# USB3_0_Console.net
KiCad netlist of a schematic drawn in Altium Designer
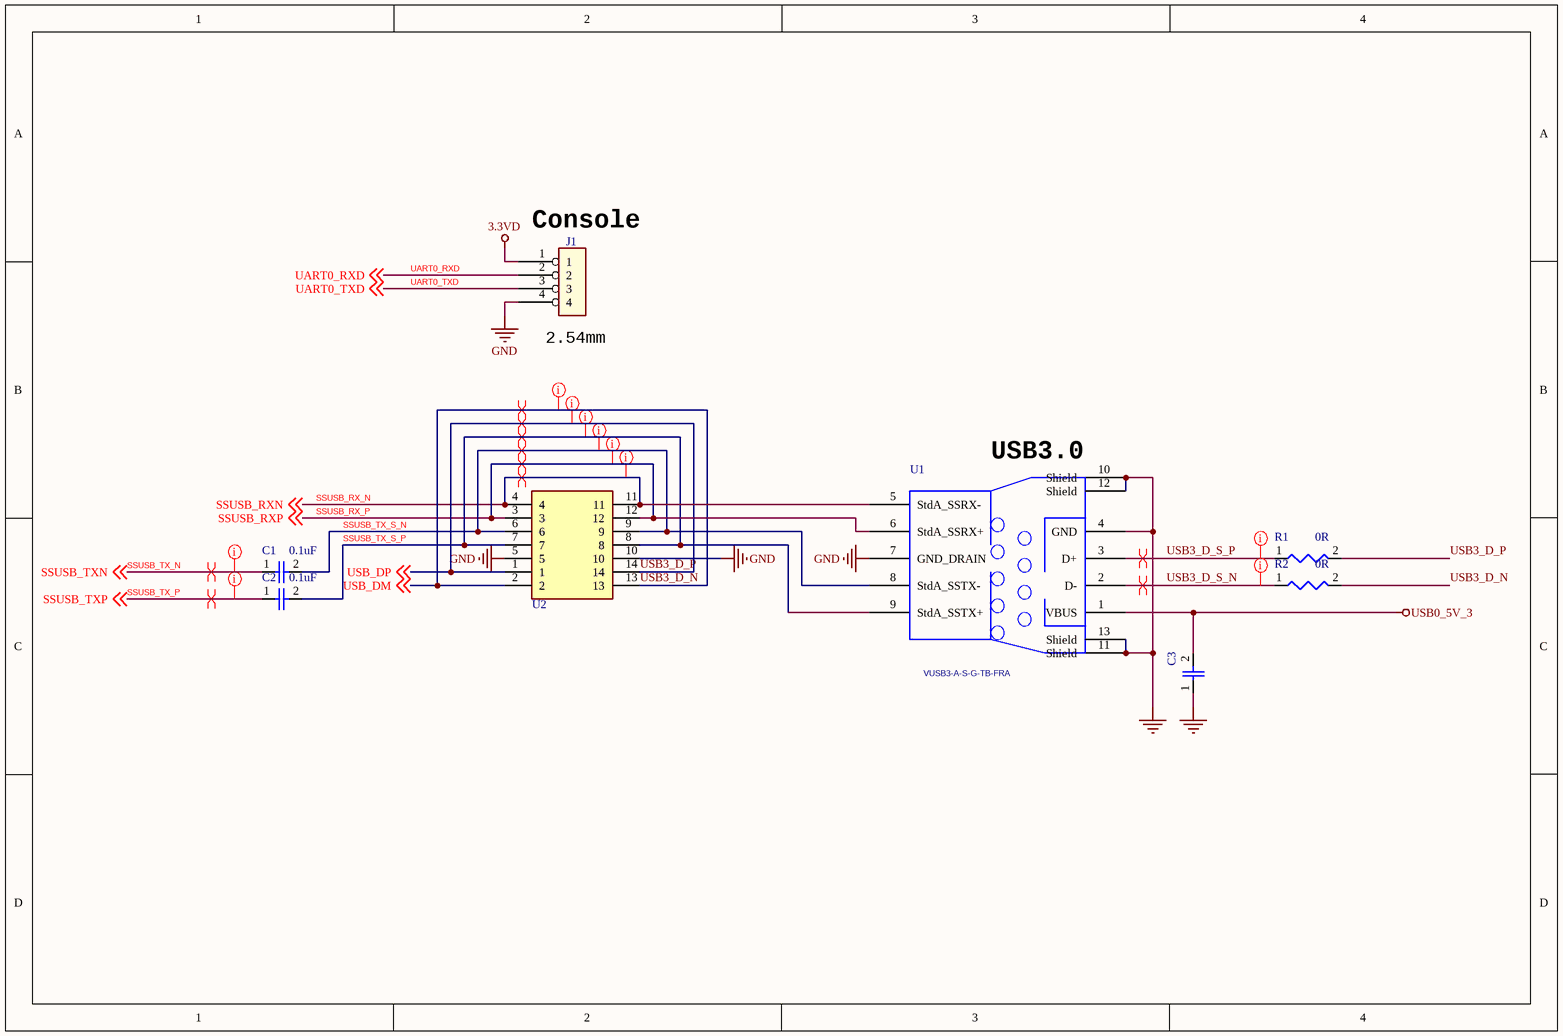
[diagram p0: USB3.0_Console.SchDoc]

(export (version "E")
  (design (tool "Eeschema 10.0.6"))
  (components
    (comp (ref "C1") (value "0.1uF") (footprint "0402-C") (libsource (lib "OOLITEV8") (part "CAP")))
    (comp (ref "C2") (value "0.1uF") (footprint "0402-C") (libsource (lib "OOLITEV8") (part "CAP")))
    (comp (ref "C3") (value "22uF,10V,0805") (footprint "0805-C") (libsource (lib "OOLITEV8") (part "CAP")))
    (comp (ref "J1")
      (value "HEADER 4x1")
      (footprint "CONN_4X1")
      (libsource (lib "OOLITEV8") (part "HEADER 4x1"))
    )
    (comp (ref "R1") (value "0R") (footprint "0402-R") (libsource (lib "OOLITEV8") (part "Res")))
    (comp (ref "R2") (value "0R") (footprint "0402-R") (libsource (lib "OOLITEV8") (part "Res")))
    (comp (ref "U1")
      (value "VUSB3-A-S-G-TB-FRA")
      (footprint "VALCON_VUSB3-A-S-G-TB-FRA")
      (description "USB 3 Type A Right Angle Vertical Socket")
      (libsource (lib "OOLITEV8") (part "VUSB3-A-S-G-TB-FRA"))
    )
    (comp (ref "U2")
      (value "SP3011-06UTG")
      (footprint "SON50P350X135X55-14N")
      (description "7V _Typ_ Clamp 4A _8/20Âµs_ Ipp Tvs Diode Surface Mount 14-UDFN _3.5x1.35_")
      (fields (field (name "MP") "SP3012-06UTG") (field (name "MF") "Littelfuse Inc."))
      (libsource (lib "OOLITEV8") (part "SP3012-06UTG"))
    )
  )
  (nets
    (net (code "1") (name "/SSUSB_TX_S_N") (class "Default")
      (node (ref "C1") (pin "2") (pinfunction "2_2") (pintype "passive"))
      (node (ref "U1") (pin "8") (pinfunction "StdA_SSTX-_8") (pintype "passive"))
      (node (ref "U2") (pin "6") (pinfunction "6_6") (pintype "passive"))
      (node (ref "U2") (pin "9") (pinfunction "9_9") (pintype "passive"))
    )
    (net (code "2") (name "/SSUSB_TX_S_P") (class "Default")
      (node (ref "C2") (pin "2") (pinfunction "2_2") (pintype "passive"))
      (node (ref "U1") (pin "9") (pinfunction "StdA_SSTX+_9") (pintype "passive"))
      (node (ref "U2") (pin "7") (pinfunction "7_7") (pintype "passive"))
      (node (ref "U2") (pin "8") (pinfunction "8_8") (pintype "passive"))
    )
    (net (code "3") (name "/USB3_D_S_N") (class "Default")
      (node (ref "R2") (pin "1") (pinfunction "1_1") (pintype "passive"))
      (node (ref "U1") (pin "2") (pinfunction "D-_2") (pintype "passive"))
    )
    (net (code "4") (name "/USB3_D_S_P") (class "Default")
      (node (ref "R1") (pin "1") (pinfunction "1_1") (pintype "passive"))
      (node (ref "U1") (pin "3") (pinfunction "D+_3") (pintype "passive"))
    )
    (net (code "5") (name "3.3VD") (class "Default")
      (node (ref "J1") (pin "1") (pinfunction "1_1") (pintype "passive"))
    )
    (net (code "6") (name "GND") (class "Default")
      (node (ref "C3") (pin "1") (pinfunction "1_1") (pintype "passive"))
      (node (ref "J1") (pin "4") (pinfunction "4_4") (pintype "passive"))
      (node (ref "U1") (pin "10") (pinfunction "Shield_10") (pintype "passive"))
      (node (ref "U1") (pin "11") (pinfunction "Shield_11") (pintype "passive"))
      (node (ref "U1") (pin "12") (pinfunction "Shield_12") (pintype "passive"))
      (node (ref "U1") (pin "13") (pinfunction "Shield_13") (pintype "passive"))
      (node (ref "U1") (pin "4") (pinfunction "GND_4") (pintype "passive"))
      (node (ref "U1") (pin "7") (pinfunction "GND_DRAIN_7") (pintype "passive"))
      (node (ref "U2") (pin "10") (pinfunction "10_10") (pintype "passive"))
      (node (ref "U2") (pin "5") (pinfunction "5_5") (pintype "passive"))
    )
    (net (code "7") (name "SSUSB_RXN") (class "Default")
      (node (ref "U1") (pin "5") (pinfunction "StdA_SSRX-_5") (pintype "passive"))
      (node (ref "U2") (pin "11") (pinfunction "11_11") (pintype "passive"))
      (node (ref "U2") (pin "4") (pinfunction "4_4") (pintype "passive"))
    )
    (net (code "8") (name "SSUSB_RXP") (class "Default")
      (node (ref "U1") (pin "6") (pinfunction "StdA_SSRX+_6") (pintype "passive"))
      (node (ref "U2") (pin "12") (pinfunction "12_12") (pintype "passive"))
      (node (ref "U2") (pin "3") (pinfunction "3_3") (pintype "passive"))
    )
    (net (code "9") (name "SSUSB_TXN") (class "Default")
      (node (ref "C1") (pin "1") (pinfunction "1_1") (pintype "passive"))
    )
    (net (code "10") (name "SSUSB_TXP") (class "Default")
      (node (ref "C2") (pin "1") (pinfunction "1_1") (pintype "passive"))
    )
    (net (code "11") (name "UART0_RXD") (class "Default")
      (node (ref "J1") (pin "2") (pinfunction "2_2") (pintype "passive"))
    )
    (net (code "12") (name "UART0_TXD") (class "Default")
      (node (ref "J1") (pin "3") (pinfunction "3_3") (pintype "passive"))
    )
    (net (code "13") (name "USB0_5V_3") (class "Default")
      (node (ref "C3") (pin "2") (pinfunction "2_2") (pintype "passive"))
      (node (ref "U1") (pin "1") (pinfunction "VBUS_1") (pintype "passive"))
    )
    (net (code "14") (name "USB_DM") (class "Default")
      (node (ref "R2") (pin "2") (pinfunction "2_2") (pintype "passive"))
      (node (ref "U2") (pin "13") (pinfunction "13_13") (pintype "passive"))
      (node (ref "U2") (pin "2") (pinfunction "2_2") (pintype "passive"))
    )
    (net (code "15") (name "USB_DP") (class "Default")
      (node (ref "R1") (pin "2") (pinfunction "2_2") (pintype "passive"))
      (node (ref "U2") (pin "1") (pinfunction "1_1") (pintype "passive"))
      (node (ref "U2") (pin "14") (pinfunction "14_14") (pintype "passive"))
    )
  )
)
